# oresat0-minusz-end-cap.net
KiCad netlist of a schematic drawn in EAGLE
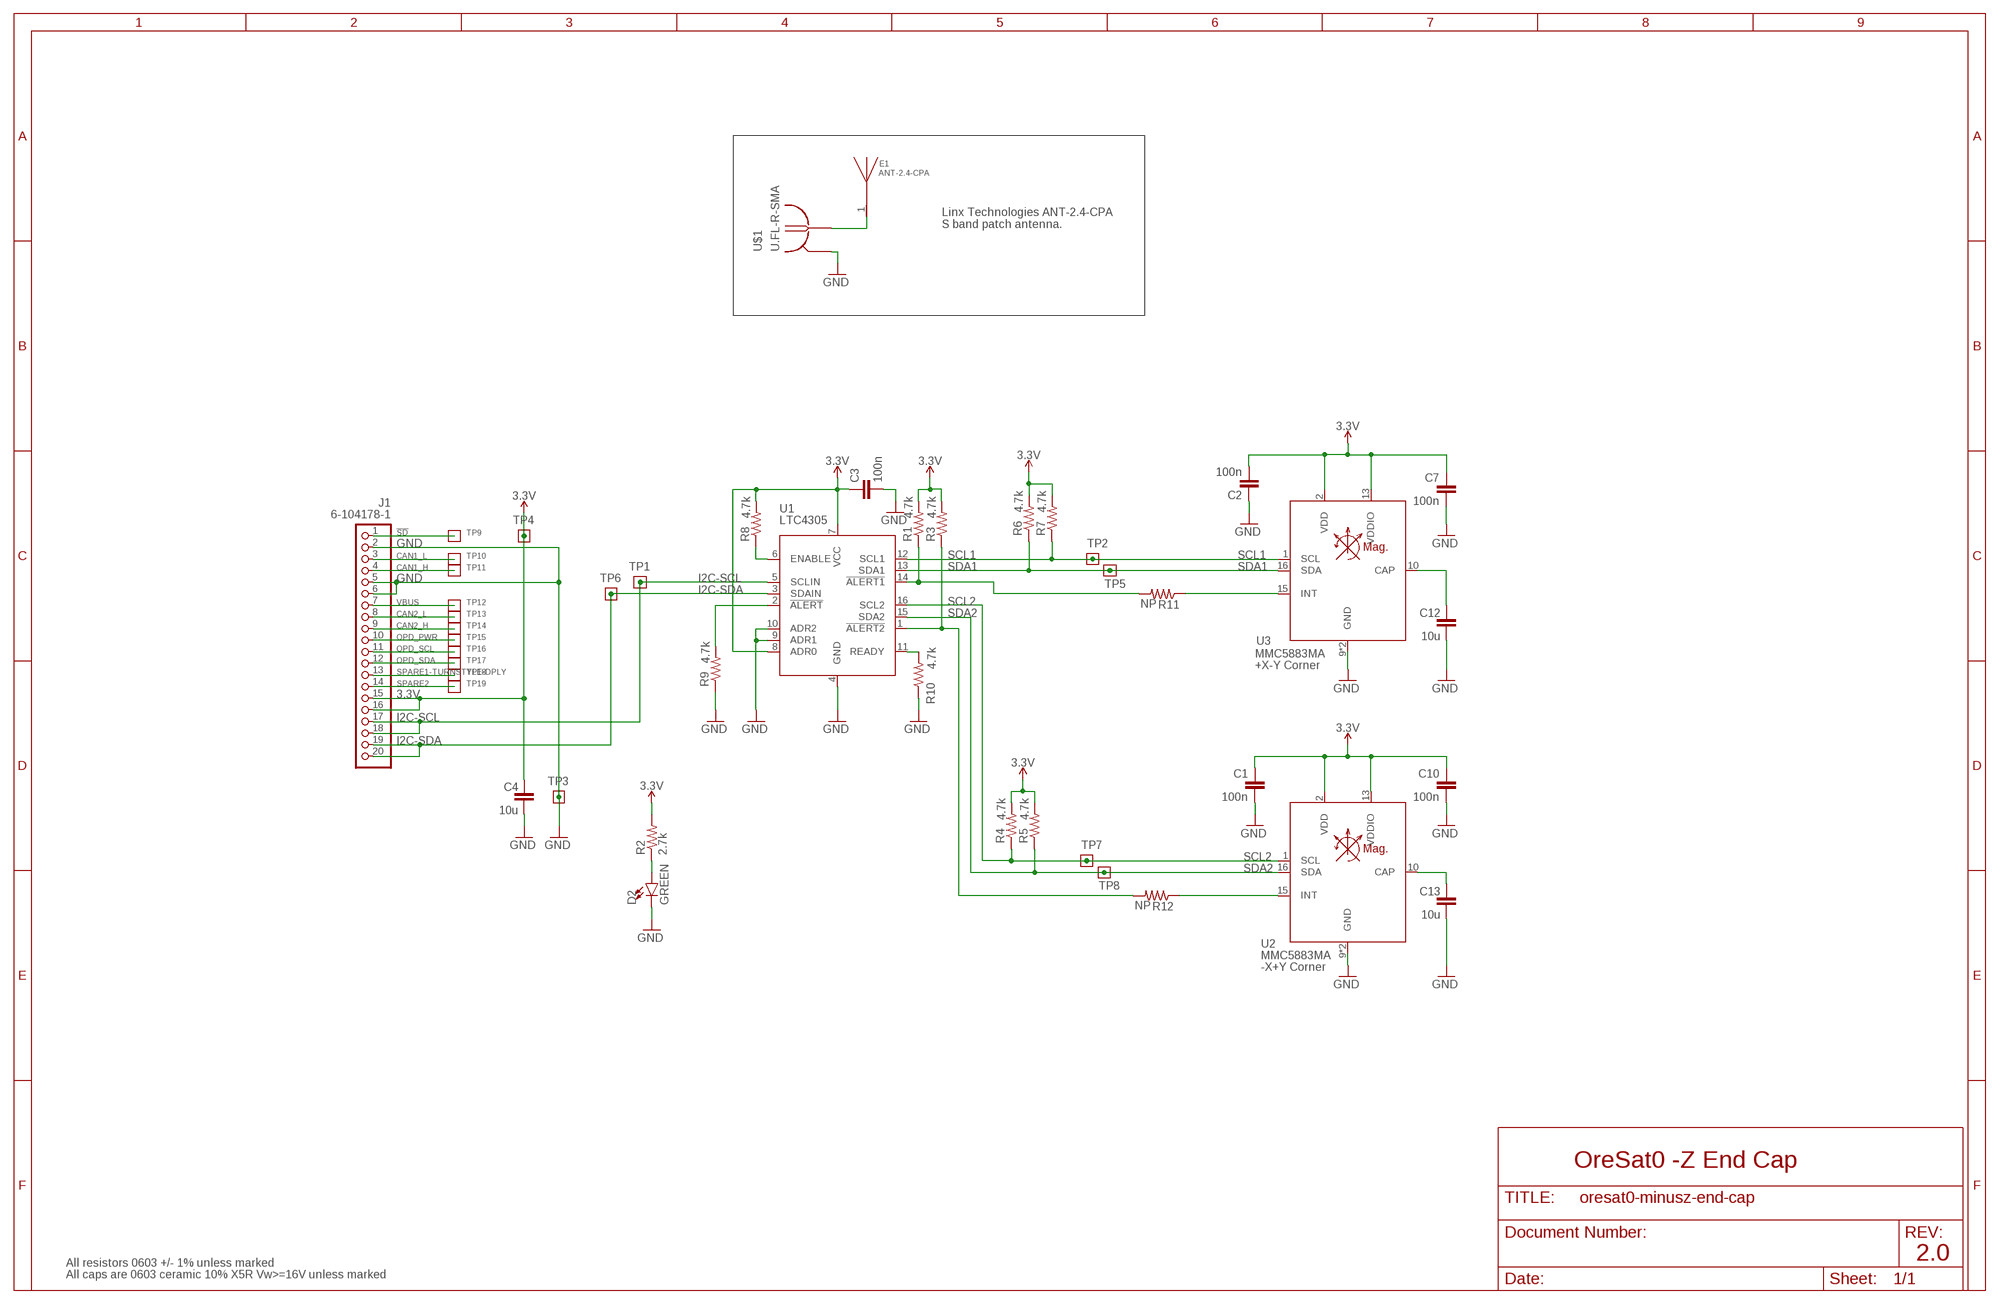
[diagram p0: schematic, sheet 1]

(export (version "E")
  (design (tool "Eeschema 10.0.6"))
  (components
    (comp (ref "C1")
      (value "100n")
      (footprint "eagle-import:.0603-B-NOSILK")
      (fields (field (name "MFR") "Samsung") (field (name "MPN") "CL10B104KB8NNNL"))
      (libsource (lib "eagle-import") (part "C-EU0603-B-NOSILK"))
    )
    (comp (ref "C2")
      (value "100n")
      (footprint "eagle-import:.0603-B-NOSILK")
      (fields (field (name "MFR") "Samsung") (field (name "MPN") "CL10B104KB8NNNL"))
      (libsource (lib "eagle-import") (part "C-EU0603-B-NOSILK"))
    )
    (comp (ref "C3")
      (value "100n")
      (footprint "eagle-import:.0603-B-NOSILK")
      (fields (field (name "MFR") "Samsung") (field (name "MPN") "CL10B104KB8NNNL"))
      (libsource (lib "eagle-import") (part "C-EU0603-B-NOSILK"))
    )
    (comp (ref "C4")
      (value "10u")
      (footprint "eagle-import:.0603-B-NOSILK")
      (fields (field (name "MFR") "Murata") (field (name "MPN") "GRM188D71A106KA73D"))
      (libsource (lib "eagle-import") (part "C-EU0603-B-NOSILK"))
    )
    (comp (ref "C7")
      (value "100n")
      (footprint "eagle-import:.0603-B-NOSILK")
      (fields (field (name "MFR") "Samsung") (field (name "MPN") "CL10B104KB8NNNL"))
      (libsource (lib "eagle-import") (part "C-EU0603-B-NOSILK"))
    )
    (comp (ref "C10")
      (value "100n")
      (footprint "eagle-import:.0603-B-NOSILK")
      (fields (field (name "MFR") "Samsung") (field (name "MPN") "CL10B104KB8NNNL"))
      (libsource (lib "eagle-import") (part "C-EU0603-B-NOSILK"))
    )
    (comp (ref "C12")
      (value "10u")
      (footprint "eagle-import:.0603-B-NOSILK")
      (fields (field (name "MFR") "Murata") (field (name "MPN") "GRM188D71A106KA73D"))
      (libsource (lib "eagle-import") (part "C-EU0603-B-NOSILK"))
    )
    (comp (ref "C13")
      (value "10u")
      (footprint "eagle-import:.0603-B-NOSILK")
      (fields (field (name "MFR") "Murata") (field (name "MPN") "GRM188D71A106KA73D"))
      (libsource (lib "eagle-import") (part "C-EU0603-B-NOSILK"))
    )
    (comp (ref "D2")
      (value "GREEN")
      (footprint "eagle-import:LED-0603")
      (fields (field (name "MFR") "Rohm") (field (name "MPN") "SML-E12M8WT86"))
      (libsource (lib "eagle-import") (part "LED-GREEN0603"))
    )
    (comp (ref "E1")
      (value "ANT-2.4-CPA")
      (footprint "eagle-import:XDCR_ANT-2.4-CPA")
      (fields
        (field (name "DIGI-KEY_PART_NUMBER") "343-ANT-2.4-CPA-ND")
        (field (name "MF") "Linx Technologies")
      )
      (libsource (lib "eagle-import") (part "ANT-2.4-CPA"))
    )
    (comp (ref "J1")
      (value "6-104178-1")
      (footprint "eagle-import:6-104178-1")
      (fields (field (name "MFR") "TE Connectivity"))
      (libsource (lib "eagle-import") (part "6-104178-1"))
    )
    (comp (ref "R1")
      (value "4.7k")
      (footprint "eagle-import:.0603-B-NOSILK")
      (fields (field (name "MFR") "TE Connectivity") (field (name "MPN") "CRGCQ0603F4K7"))
      (libsource (lib "eagle-import") (part "R-US_0603-B-NOSILK"))
    )
    (comp (ref "R2")
      (value "2.7k")
      (footprint "eagle-import:.0603-B-NOSILK")
      (fields (field (name "MFR") "TE Connectivity") (field (name "MPN") "CRGCQ0603F2K7"))
      (libsource (lib "eagle-import") (part "R-US_0603-B-NOSILK"))
    )
    (comp (ref "R3")
      (value "4.7k")
      (footprint "eagle-import:.0603-B-NOSILK")
      (fields (field (name "MFR") "TE Connectivity") (field (name "MPN") "CRGCQ0603F4K7"))
      (libsource (lib "eagle-import") (part "R-US_0603-B-NOSILK"))
    )
    (comp (ref "R4")
      (value "4.7k")
      (footprint "eagle-import:.0603-B-NOSILK")
      (fields (field (name "MFR") "TE Connectivity") (field (name "MPN") "CRGCQ0603F4K7"))
      (libsource (lib "eagle-import") (part "R-US_0603-B-NOSILK"))
    )
    (comp (ref "R5")
      (value "4.7k")
      (footprint "eagle-import:.0603-B-NOSILK")
      (fields (field (name "MFR") "TE Connectivity") (field (name "MPN") "CRGCQ0603F4K7"))
      (libsource (lib "eagle-import") (part "R-US_0603-B-NOSILK"))
    )
    (comp (ref "R6")
      (value "4.7k")
      (footprint "eagle-import:.0603-B-NOSILK")
      (fields (field (name "MFR") "TE Connectivity") (field (name "MPN") "CRGCQ0603F4K7"))
      (libsource (lib "eagle-import") (part "R-US_0603-B-NOSILK"))
    )
    (comp (ref "R7")
      (value "4.7k")
      (footprint "eagle-import:.0603-B-NOSILK")
      (fields (field (name "MFR") "TE Connectivity") (field (name "MPN") "CRGCQ0603F4K7"))
      (libsource (lib "eagle-import") (part "R-US_0603-B-NOSILK"))
    )
    (comp (ref "R8")
      (value "4.7k")
      (footprint "eagle-import:.0603-B-NOSILK")
      (fields (field (name "MFR") "TE Connectivity") (field (name "MPN") "CRGCQ0603F4K7"))
      (libsource (lib "eagle-import") (part "R-US_0603-B-NOSILK"))
    )
    (comp (ref "R9")
      (value "4.7k")
      (footprint "eagle-import:.0603-B-NOSILK")
      (fields (field (name "MFR") "TE Connectivity") (field (name "MPN") "CRGCQ0603F4K7"))
      (libsource (lib "eagle-import") (part "R-US_0603-B-NOSILK"))
    )
    (comp (ref "R10")
      (value "4.7k")
      (footprint "eagle-import:.0603-B-NOSILK")
      (fields (field (name "MFR") "TE Connectivity") (field (name "MPN") "CRGCQ0603F4K7"))
      (libsource (lib "eagle-import") (part "R-US_0603-B-NOSILK"))
    )
    (comp (ref "R11")
      (value "NP")
      (footprint "eagle-import:.0603-B-NOSILK")
      (libsource (lib "eagle-import") (part "R-US_0603-B-NOSILK"))
    )
    (comp (ref "R12")
      (value "NP")
      (footprint "eagle-import:.0603-B-NOSILK")
      (libsource (lib "eagle-import") (part "R-US_0603-B-NOSILK"))
    )
    (comp (ref "TP1")
      (value "TEST-POINT-LARGE-SQUARE")
      (footprint "eagle-import:1X01")
      (libsource (lib "eagle-import") (part "TEST-POINT-LARGE-SQUARE"))
    )
    (comp (ref "TP2")
      (value "TEST-POINT-LARGE-SQUARE")
      (footprint "eagle-import:1X01")
      (libsource (lib "eagle-import") (part "TEST-POINT-LARGE-SQUARE"))
    )
    (comp (ref "TP3")
      (value "TEST-POINT-LARGE-SQUARE")
      (footprint "eagle-import:1X01")
      (libsource (lib "eagle-import") (part "TEST-POINT-LARGE-SQUARE"))
    )
    (comp (ref "TP4")
      (value "TEST-POINT-LARGE-SQUARE")
      (footprint "eagle-import:1X01")
      (libsource (lib "eagle-import") (part "TEST-POINT-LARGE-SQUARE"))
    )
    (comp (ref "TP5")
      (value "TEST-POINT-LARGE-SQUARE")
      (footprint "eagle-import:1X01")
      (libsource (lib "eagle-import") (part "TEST-POINT-LARGE-SQUARE"))
    )
    (comp (ref "TP6")
      (value "TEST-POINT-LARGE-SQUARE")
      (footprint "eagle-import:1X01")
      (libsource (lib "eagle-import") (part "TEST-POINT-LARGE-SQUARE"))
    )
    (comp (ref "TP7")
      (value "TEST-POINT-LARGE-SQUARE")
      (footprint "eagle-import:1X01")
      (libsource (lib "eagle-import") (part "TEST-POINT-LARGE-SQUARE"))
    )
    (comp (ref "TP8")
      (value "TEST-POINT-LARGE-SQUARE")
      (footprint "eagle-import:1X01")
      (libsource (lib "eagle-import") (part "TEST-POINT-LARGE-SQUARE"))
    )
    (comp (ref "TP9")
      (value "TEST-POINT-LARGE-SQUARE")
      (footprint "eagle-import:1X01")
      (libsource (lib "eagle-import") (part "TEST-POINT-LARGE-SQUARE"))
    )
    (comp (ref "TP10")
      (value "TEST-POINT-LARGE-SQUARE")
      (footprint "eagle-import:1X01")
      (libsource (lib "eagle-import") (part "TEST-POINT-LARGE-SQUARE"))
    )
    (comp (ref "TP11")
      (value "TEST-POINT-LARGE-SQUARE")
      (footprint "eagle-import:1X01")
      (libsource (lib "eagle-import") (part "TEST-POINT-LARGE-SQUARE"))
    )
    (comp (ref "TP12")
      (value "TEST-POINT-LARGE-SQUARE")
      (footprint "eagle-import:1X01")
      (libsource (lib "eagle-import") (part "TEST-POINT-LARGE-SQUARE"))
    )
    (comp (ref "TP13")
      (value "TEST-POINT-LARGE-SQUARE")
      (footprint "eagle-import:1X01")
      (libsource (lib "eagle-import") (part "TEST-POINT-LARGE-SQUARE"))
    )
    (comp (ref "TP14")
      (value "TEST-POINT-LARGE-SQUARE")
      (footprint "eagle-import:1X01")
      (libsource (lib "eagle-import") (part "TEST-POINT-LARGE-SQUARE"))
    )
    (comp (ref "TP15")
      (value "TEST-POINT-LARGE-SQUARE")
      (footprint "eagle-import:1X01")
      (libsource (lib "eagle-import") (part "TEST-POINT-LARGE-SQUARE"))
    )
    (comp (ref "TP16")
      (value "TEST-POINT-LARGE-SQUARE")
      (footprint "eagle-import:1X01")
      (libsource (lib "eagle-import") (part "TEST-POINT-LARGE-SQUARE"))
    )
    (comp (ref "TP17")
      (value "TEST-POINT-LARGE-SQUARE")
      (footprint "eagle-import:1X01")
      (libsource (lib "eagle-import") (part "TEST-POINT-LARGE-SQUARE"))
    )
    (comp (ref "TP18")
      (value "TEST-POINT-LARGE-SQUARE")
      (footprint "eagle-import:1X01")
      (libsource (lib "eagle-import") (part "TEST-POINT-LARGE-SQUARE"))
    )
    (comp (ref "TP19")
      (value "TEST-POINT-LARGE-SQUARE")
      (footprint "eagle-import:1X01")
      (libsource (lib "eagle-import") (part "TEST-POINT-LARGE-SQUARE"))
    )
    (comp (ref "U$1")
      (value "U.FL-R-SMA")
      (footprint "eagle-import:U.FL-R-SMT")
      (libsource (lib "eagle-import") (part "U.FL-R-SMA"))
    )
    (comp (ref "U1")
      (value "LTC4305")
      (footprint "eagle-import:16-SSOP")
      (fields (field (name "MFR") "Analog") (field (name "MPN") "LTC4305IGN#PBF"))
      (libsource (lib "eagle-import") (part "LTC4305"))
    )
    (comp (ref "U2")
      (value "MMC5883MA")
      (footprint "eagle-import:LGA-16(3X3)")
      (fields (field (name "MFR") "Memsic"))
      (libsource (lib "eagle-import") (part "MMC5883MA"))
    )
    (comp (ref "U3")
      (value "MMC5883MA")
      (footprint "eagle-import:LGA-16(3X3)")
      (fields (field (name "MFR") "Memsic"))
      (libsource (lib "eagle-import") (part "MMC5883MA"))
    )
  )
  (nets
    (net (code "1") (name "/CAN1_H") (class "Default")
      (node (ref "J1") (pin "4") (pinfunction "4_4") (pintype "passive"))
      (node (ref "TP11") (pin "1") (pinfunction "1_1") (pintype "passive"))
    )
    (net (code "2") (name "/CAN1_L") (class "Default")
      (node (ref "J1") (pin "3") (pinfunction "3_3") (pintype "passive"))
      (node (ref "TP10") (pin "1") (pinfunction "1_1") (pintype "passive"))
    )
    (net (code "3") (name "/CAN2_H") (class "Default")
      (node (ref "J1") (pin "9") (pinfunction "9_9") (pintype "passive"))
      (node (ref "TP14") (pin "1") (pinfunction "1_1") (pintype "passive"))
    )
    (net (code "4") (name "/CAN2_L") (class "Default")
      (node (ref "J1") (pin "8") (pinfunction "8_8") (pintype "passive"))
      (node (ref "TP13") (pin "1") (pinfunction "1_1") (pintype "passive"))
    )
    (net (code "5") (name "/I2C-SCL") (class "Default")
      (node (ref "J1") (pin "17") (pinfunction "17_17") (pintype "passive"))
      (node (ref "J1") (pin "18") (pinfunction "18_18") (pintype "passive"))
      (node (ref "TP1") (pin "1") (pinfunction "1_1") (pintype "passive"))
      (node (ref "U1") (pin "5") (pinfunction "SCLIN_5") (pintype "bidirectional"))
    )
    (net (code "6") (name "/I2C-SDA") (class "Default")
      (node (ref "J1") (pin "19") (pinfunction "19_19") (pintype "passive"))
      (node (ref "J1") (pin "20") (pinfunction "20_20") (pintype "passive"))
      (node (ref "TP6") (pin "1") (pinfunction "1_1") (pintype "passive"))
      (node (ref "U1") (pin "3") (pinfunction "SDAIN_3") (pintype "bidirectional"))
    )
    (net (code "7") (name "/OPD_PWR") (class "Default")
      (node (ref "J1") (pin "10") (pinfunction "10_10") (pintype "passive"))
      (node (ref "TP15") (pin "1") (pinfunction "1_1") (pintype "passive"))
    )
    (net (code "8") (name "/OPD_SCL") (class "Default")
      (node (ref "J1") (pin "11") (pinfunction "11_11") (pintype "passive"))
      (node (ref "TP16") (pin "1") (pinfunction "1_1") (pintype "passive"))
    )
    (net (code "9") (name "/OPD_SDA") (class "Default")
      (node (ref "J1") (pin "12") (pinfunction "12_12") (pintype "passive"))
      (node (ref "TP17") (pin "1") (pinfunction "1_1") (pintype "passive"))
    )
    (net (code "10") (name "/SCL1") (class "Default")
      (node (ref "R7") (pin "1") (pinfunction "1_1") (pintype "passive"))
      (node (ref "TP2") (pin "1") (pinfunction "1_1") (pintype "passive"))
      (node (ref "U1") (pin "12") (pinfunction "SCL1_12") (pintype "bidirectional"))
      (node (ref "U3") (pin "1") (pinfunction "SCL_1") (pintype "input"))
    )
    (net (code "11") (name "/SCL2") (class "Default")
      (node (ref "R4") (pin "1") (pinfunction "1_1") (pintype "passive"))
      (node (ref "TP7") (pin "1") (pinfunction "1_1") (pintype "passive"))
      (node (ref "U1") (pin "16") (pinfunction "SCL2_16") (pintype "bidirectional"))
      (node (ref "U2") (pin "1") (pinfunction "SCL_1") (pintype "input"))
    )
    (net (code "12") (name "/SDA1") (class "Default")
      (node (ref "R6") (pin "1") (pinfunction "1_1") (pintype "passive"))
      (node (ref "TP5") (pin "1") (pinfunction "1_1") (pintype "passive"))
      (node (ref "U1") (pin "13") (pinfunction "SDA1_13") (pintype "bidirectional"))
      (node (ref "U3") (pin "16") (pinfunction "SDA_16") (pintype "bidirectional"))
    )
    (net (code "13") (name "/SDA2") (class "Default")
      (node (ref "R5") (pin "1") (pinfunction "1_1") (pintype "passive"))
      (node (ref "TP8") (pin "1") (pinfunction "1_1") (pintype "passive"))
      (node (ref "U1") (pin "15") (pinfunction "SDA2_15") (pintype "bidirectional"))
      (node (ref "U2") (pin "16") (pinfunction "SDA_16") (pintype "bidirectional"))
    )
    (net (code "14") (name "/SPARE1-TURNSTYLE-DPLY") (class "Default")
      (node (ref "J1") (pin "13") (pinfunction "13_13") (pintype "passive"))
      (node (ref "TP18") (pin "1") (pinfunction "1_1") (pintype "passive"))
    )
    (net (code "15") (name "/SPARE2") (class "Default")
      (node (ref "J1") (pin "14") (pinfunction "14_14") (pintype "passive"))
      (node (ref "TP19") (pin "1") (pinfunction "1_1") (pintype "passive"))
    )
    (net (code "16") (name "/VBUS") (class "Default")
      (node (ref "J1") (pin "7") (pinfunction "7_7") (pintype "passive"))
      (node (ref "TP12") (pin "1") (pinfunction "1_1") (pintype "passive"))
    )
    (net (code "17") (name "/~{SD}") (class "Default")
      (node (ref "J1") (pin "1") (pinfunction "1_1") (pintype "passive"))
      (node (ref "TP9") (pin "1") (pinfunction "1_1") (pintype "passive"))
    )
    (net (code "18") (name "3.3V") (class "Default")
      (node (ref "C1") (pin "1") (pinfunction "1_1") (pintype "passive"))
      (node (ref "C10") (pin "1") (pinfunction "1_1") (pintype "passive"))
      (node (ref "C2") (pin "2") (pinfunction "2_2") (pintype "passive"))
      (node (ref "C3") (pin "1") (pinfunction "1_1") (pintype "passive"))
      (node (ref "C4") (pin "1") (pinfunction "1_1") (pintype "passive"))
      (node (ref "C7") (pin "1") (pinfunction "1_1") (pintype "passive"))
      (node (ref "J1") (pin "15") (pinfunction "15_15") (pintype "passive"))
      (node (ref "J1") (pin "16") (pinfunction "16_16") (pintype "passive"))
      (node (ref "R1") (pin "2") (pinfunction "2_2") (pintype "passive"))
      (node (ref "R2") (pin "2") (pinfunction "2_2") (pintype "passive"))
      (node (ref "R3") (pin "2") (pinfunction "2_2") (pintype "passive"))
      (node (ref "R4") (pin "2") (pinfunction "2_2") (pintype "passive"))
      (node (ref "R5") (pin "2") (pinfunction "2_2") (pintype "passive"))
      (node (ref "R6") (pin "2") (pinfunction "2_2") (pintype "passive"))
      (node (ref "R7") (pin "2") (pinfunction "2_2") (pintype "passive"))
      (node (ref "R8") (pin "2") (pinfunction "2_2") (pintype "passive"))
      (node (ref "TP4") (pin "1") (pinfunction "1_1") (pintype "passive"))
      (node (ref "U1") (pin "7") (pinfunction "VCC_7") (pintype "power_in"))
      (node (ref "U1") (pin "8") (pinfunction "ADR0_8") (pintype "input"))
      (node (ref "U2") (pin "13") (pinfunction "VDDIO_13") (pintype "power_in"))
      (node (ref "U2") (pin "2") (pinfunction "VDD_2") (pintype "power_in"))
      (node (ref "U3") (pin "13") (pinfunction "VDDIO_13") (pintype "power_in"))
      (node (ref "U3") (pin "2") (pinfunction "VDD_2") (pintype "power_in"))
    )
    (net (code "19") (name "GND") (class "Default")
      (node (ref "C1") (pin "2") (pinfunction "2_2") (pintype "passive"))
      (node (ref "C10") (pin "2") (pinfunction "2_2") (pintype "passive"))
      (node (ref "C12") (pin "2") (pinfunction "2_2") (pintype "passive"))
      (node (ref "C13") (pin "2") (pinfunction "2_2") (pintype "passive"))
      (node (ref "C2") (pin "1") (pinfunction "1_1") (pintype "passive"))
      (node (ref "C3") (pin "2") (pinfunction "2_2") (pintype "passive"))
      (node (ref "C4") (pin "2") (pinfunction "2_2") (pintype "passive"))
      (node (ref "C7") (pin "2") (pinfunction "2_2") (pintype "passive"))
      (node (ref "D2") (pin "C") (pinfunction "C_C") (pintype "passive"))
      (node (ref "J1") (pin "2") (pinfunction "2_2") (pintype "passive"))
      (node (ref "J1") (pin "5") (pinfunction "5_5") (pintype "passive"))
      (node (ref "J1") (pin "6") (pinfunction "6_6") (pintype "passive"))
      (node (ref "R10") (pin "1") (pinfunction "1_1") (pintype "passive"))
      (node (ref "R9") (pin "1") (pinfunction "1_1") (pintype "passive"))
      (node (ref "TP3") (pin "1") (pinfunction "1_1") (pintype "passive"))
      (node (ref "U$1") (pin "2") (pinfunction "P$2_2") (pintype "bidirectional"))
      (node (ref "U$1") (pin "3") (pinfunction "P$2_3") (pintype "bidirectional"))
      (node (ref "U1") (pin "10") (pinfunction "ADR2_10") (pintype "input"))
      (node (ref "U1") (pin "4") (pinfunction "GND_4") (pintype "power_in"))
      (node (ref "U1") (pin "9") (pinfunction "ADR1_9") (pintype "input"))
      (node (ref "U2") (pin "11") (pinfunction "GND_11") (pintype "power_in"))
      (node (ref "U2") (pin "9") (pinfunction "GND_9") (pintype "power_in"))
      (node (ref "U3") (pin "11") (pinfunction "GND_11") (pintype "power_in"))
      (node (ref "U3") (pin "9") (pinfunction "GND_9") (pintype "power_in"))
    )
    (net (code "20") (name "Net-(D2-PadA)") (class "Default")
      (node (ref "D2") (pin "A") (pinfunction "A_A") (pintype "passive"))
      (node (ref "R2") (pin "1") (pinfunction "1_1") (pintype "passive"))
    )
    (net (code "21") (name "Net-(E1-FEED)") (class "Default")
      (node (ref "E1") (pin "1") (pinfunction "FEED_1") (pintype "input"))
      (node (ref "U$1") (pin "1") (pinfunction "P$1_1") (pintype "bidirectional"))
    )
    (net (code "22") (name "Net-(U1-ENABLE)") (class "Default")
      (node (ref "R8") (pin "1") (pinfunction "1_1") (pintype "passive"))
      (node (ref "U1") (pin "6") (pinfunction "ENABLE_6") (pintype "input"))
    )
    (net (code "23") (name "Net-(U1-READY)") (class "Default")
      (node (ref "R10") (pin "2") (pinfunction "2_2") (pintype "passive"))
      (node (ref "U1") (pin "11") (pinfunction "READY_11") (pintype "output"))
    )
    (net (code "24") (name "Net-(U1-~{ALERT1})") (class "Default")
      (node (ref "R1") (pin "1") (pinfunction "1_1") (pintype "passive"))
      (node (ref "R11") (pin "2") (pinfunction "2_2") (pintype "passive"))
      (node (ref "U1") (pin "14") (pinfunction "~{ALERT1}_14") (pintype "input"))
    )
    (net (code "25") (name "Net-(U1-~{ALERT2})") (class "Default")
      (node (ref "R12") (pin "2") (pinfunction "2_2") (pintype "passive"))
      (node (ref "R3") (pin "1") (pinfunction "1_1") (pintype "passive"))
      (node (ref "U1") (pin "1") (pinfunction "~{ALERT2}_1") (pintype "input"))
    )
    (net (code "26") (name "Net-(U1-~{ALERT})") (class "Default")
      (node (ref "R9") (pin "2") (pinfunction "2_2") (pintype "passive"))
      (node (ref "U1") (pin "2") (pinfunction "~{ALERT}_2") (pintype "output"))
    )
    (net (code "27") (name "Net-(U2-CAP)") (class "Default")
      (node (ref "C13") (pin "1") (pinfunction "1_1") (pintype "passive"))
      (node (ref "U2") (pin "10") (pinfunction "CAP_10") (pintype "power_in"))
    )
    (net (code "28") (name "Net-(U2-INT)") (class "Default")
      (node (ref "R12") (pin "1") (pinfunction "1_1") (pintype "passive"))
      (node (ref "U2") (pin "15") (pinfunction "INT_15") (pintype "output"))
    )
    (net (code "29") (name "Net-(U3-CAP)") (class "Default")
      (node (ref "C12") (pin "1") (pinfunction "1_1") (pintype "passive"))
      (node (ref "U3") (pin "10") (pinfunction "CAP_10") (pintype "power_in"))
    )
    (net (code "30") (name "Net-(U3-INT)") (class "Default")
      (node (ref "R11") (pin "1") (pinfunction "1_1") (pintype "passive"))
      (node (ref "U3") (pin "15") (pinfunction "INT_15") (pintype "output"))
    )
  )
)
